# expansion_module_ARDUINO_UNO.net
KiCad netlist of a schematic drawn in EAGLE
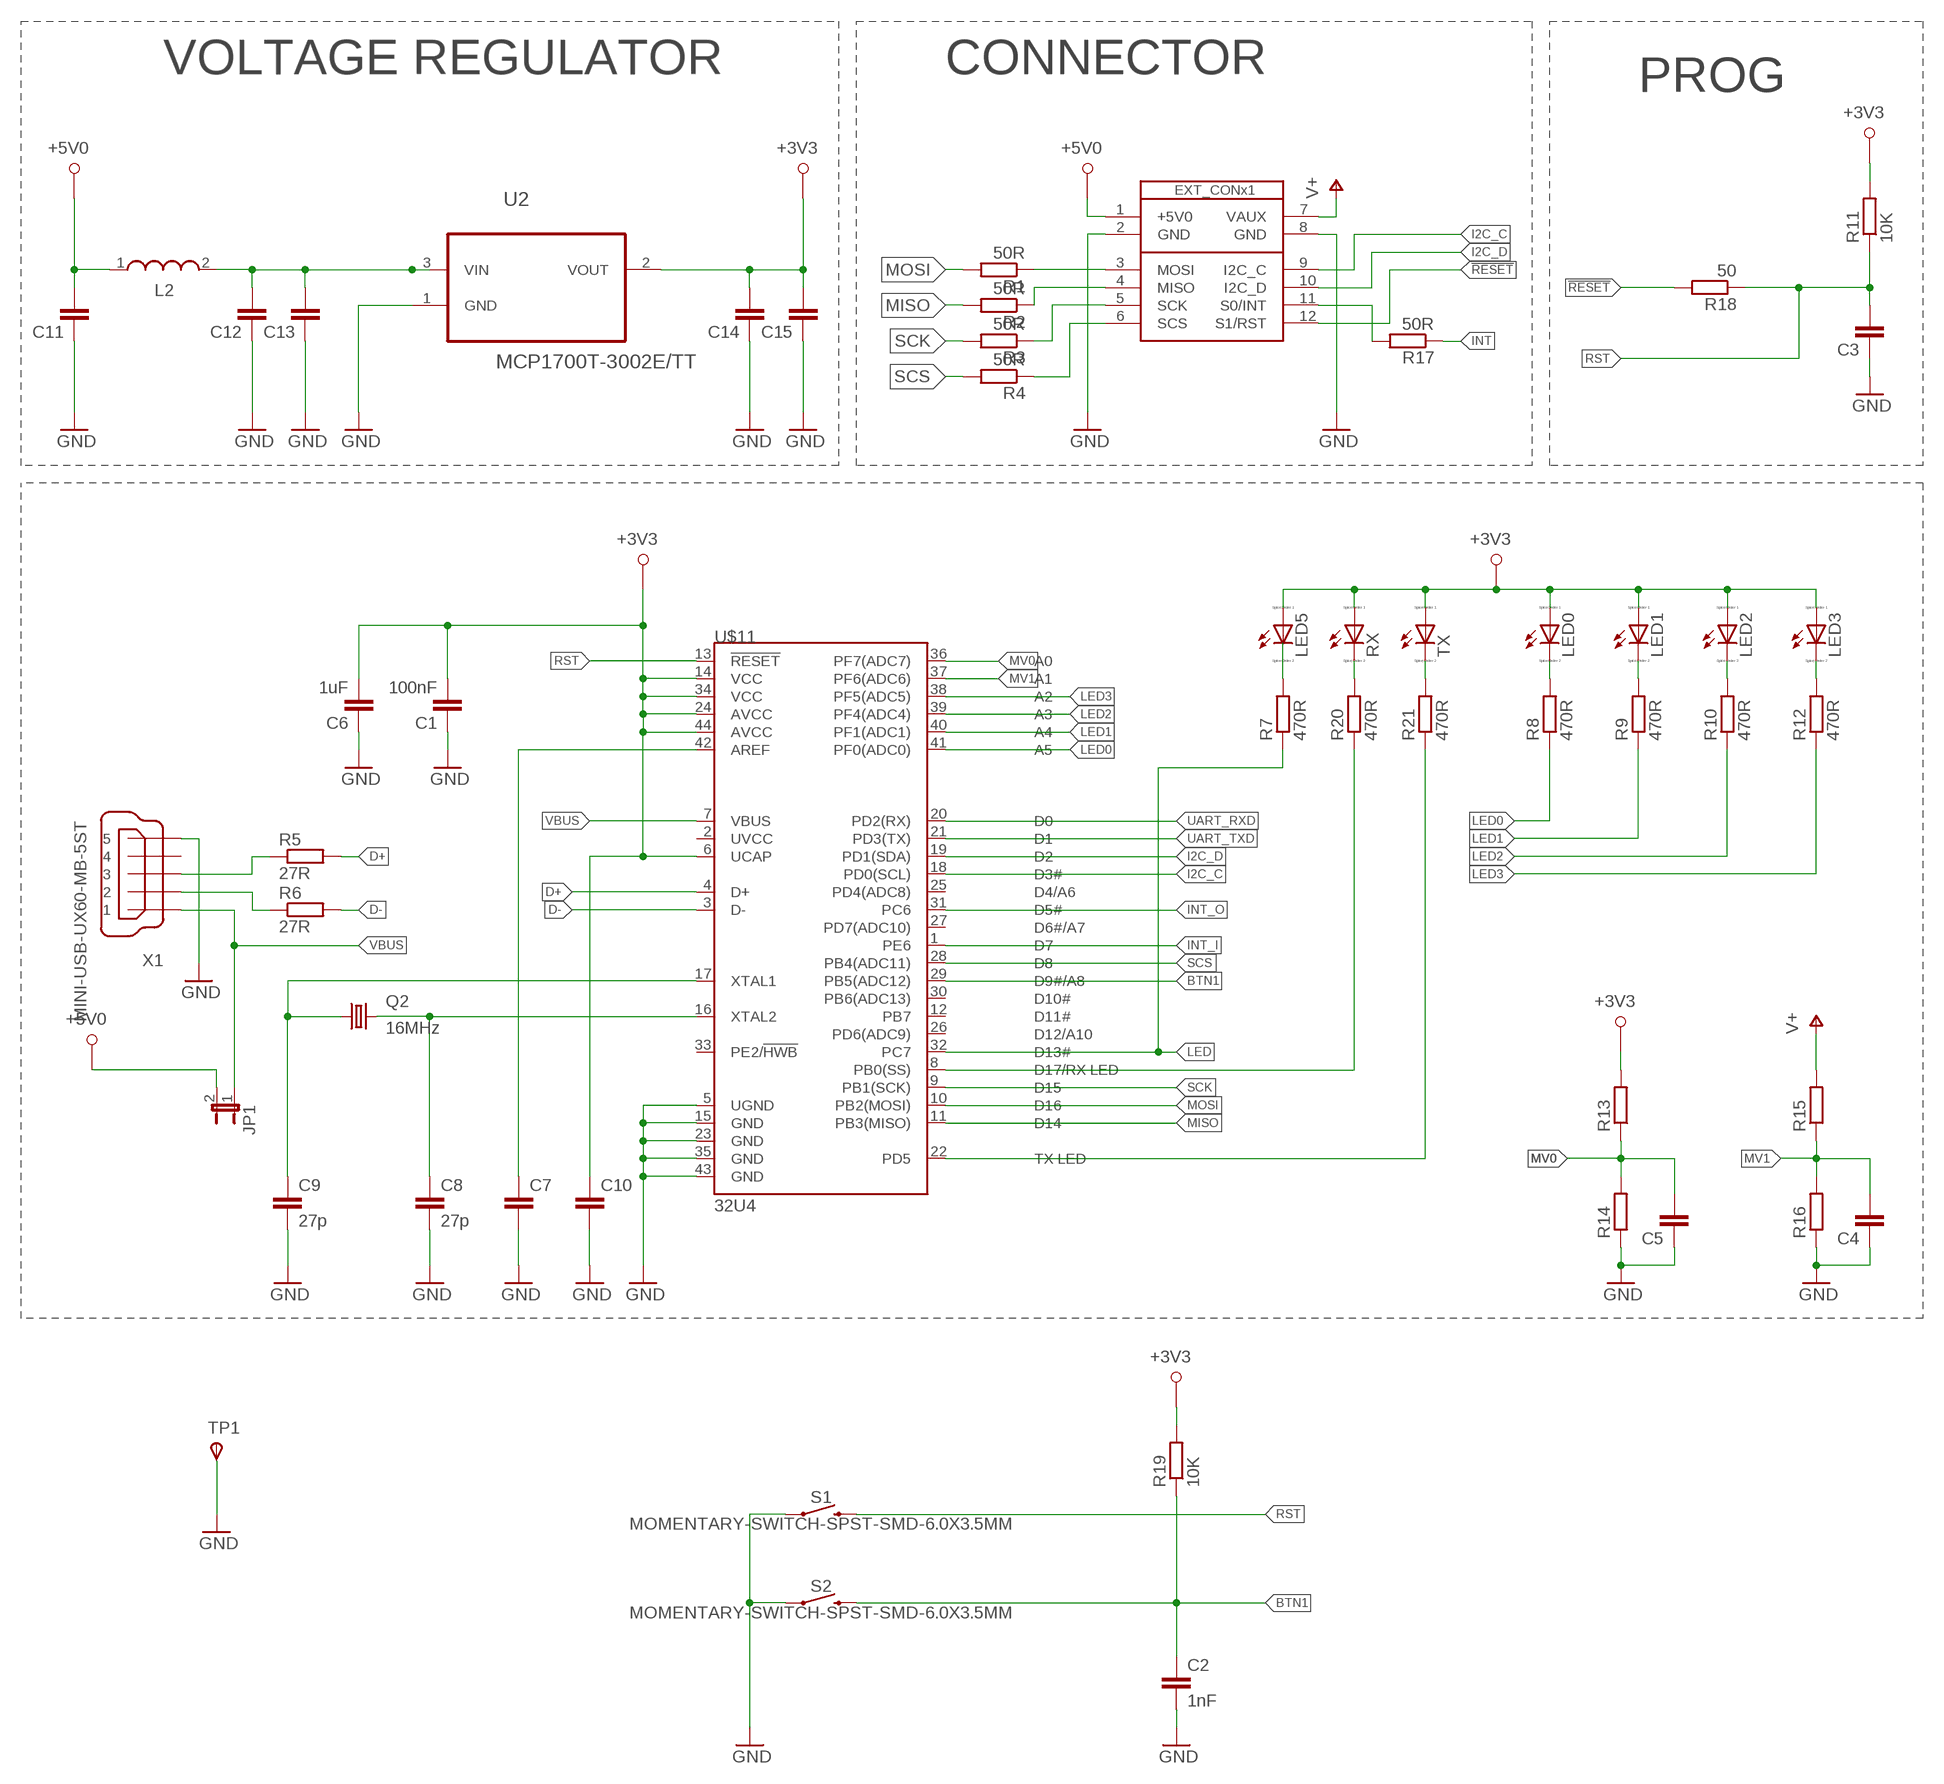
[diagram p0: schematic, sheet 1]

(export (version "E")
  (design (tool "Eeschema 10.0.6"))
  (components
    (comp (ref "C1")
      (value "100nF")
      (footprint "eagle-import:C0603")
      (libsource (lib "eagle-import") (part "resistor_C-EUC0603"))
    )
    (comp (ref "C2")
      (value "1nF")
      (footprint "eagle-import:C0603K")
      (libsource (lib "eagle-import") (part "C-EUC0603K"))
    )
    (comp (ref "C3")
      (value "C-EUC0603")
      (footprint "eagle-import:C0603")
      (libsource (lib "eagle-import") (part "resistor_C-EUC0603"))
    )
    (comp (ref "C4")
      (value "C-EUC0603")
      (footprint "eagle-import:C0603")
      (libsource (lib "eagle-import") (part "resistor_C-EUC0603"))
    )
    (comp (ref "C5")
      (value "C-EUC0603")
      (footprint "eagle-import:C0603")
      (libsource (lib "eagle-import") (part "resistor_C-EUC0603"))
    )
    (comp (ref "C6")
      (value "1uF")
      (footprint "eagle-import:C0603")
      (libsource (lib "eagle-import") (part "resistor_C-EUC0603"))
    )
    (comp (ref "C7")
      (value "C-EUC0603K")
      (footprint "eagle-import:C0603K")
      (libsource (lib "eagle-import") (part "C-EUC0603K"))
    )
    (comp (ref "C8")
      (value "27p")
      (footprint "eagle-import:C0603K")
      (libsource (lib "eagle-import") (part "C-EUC0603K"))
    )
    (comp (ref "C9")
      (value "27p")
      (footprint "eagle-import:C0603K")
      (libsource (lib "eagle-import") (part "C-EUC0603K"))
    )
    (comp (ref "C10")
      (value "C-EUC0603K")
      (footprint "eagle-import:C0603K")
      (libsource (lib "eagle-import") (part "C-EUC0603K"))
    )
    (comp (ref "C11")
      (value "C-EUC0603")
      (footprint "eagle-import:C0603")
      (libsource (lib "eagle-import") (part "resistor_C-EUC0603"))
    )
    (comp (ref "C12")
      (value "C-EUC0603")
      (footprint "eagle-import:C0603")
      (libsource (lib "eagle-import") (part "resistor_C-EUC0603"))
    )
    (comp (ref "C13")
      (value "C-EUC0603")
      (footprint "eagle-import:C0603")
      (libsource (lib "eagle-import") (part "resistor_C-EUC0603"))
    )
    (comp (ref "C14")
      (value "C-EUC0603")
      (footprint "eagle-import:C0603")
      (libsource (lib "eagle-import") (part "resistor_C-EUC0603"))
    )
    (comp (ref "C15")
      (value "C-EUC0603")
      (footprint "eagle-import:C0603")
      (libsource (lib "eagle-import") (part "resistor_C-EUC0603"))
    )
    (comp (ref "JP1")
      (value "JP1E")
      (footprint "eagle-import:JP1")
      (libsource (lib "eagle-import") (part "JP1E"))
    )
    (comp (ref "L2")
      (value "WE-LQ_1210")
      (footprint "eagle-import:WE-LQ_M")
      (libsource (lib "eagle-import") (part "WE-LQ_1210"))
    )
    (comp (ref "LED0")
      (value "LED_ESML0603")
      (footprint "eagle-import:LED_SML0603")
      (libsource (lib "eagle-import") (part "LED_ESML0603"))
    )
    (comp (ref "LED1")
      (value "LED_ESML0603")
      (footprint "eagle-import:LED_SML0603")
      (libsource (lib "eagle-import") (part "LED_ESML0603"))
    )
    (comp (ref "LED2")
      (value "LED_ESML0603")
      (footprint "eagle-import:LED_SML0603")
      (libsource (lib "eagle-import") (part "LED_ESML0603"))
    )
    (comp (ref "LED3")
      (value "LED_ESML0603")
      (footprint "eagle-import:LED_SML0603")
      (libsource (lib "eagle-import") (part "LED_ESML0603"))
    )
    (comp (ref "LED5")
      (value "LED_ESML0603")
      (footprint "eagle-import:LED_SML0603")
      (libsource (lib "eagle-import") (part "LED_ESML0603"))
    )
    (comp (ref "Q2")
      (value "16MHz")
      (footprint "eagle-import:5.0X3.2_KX-9A")
      (libsource (lib "eagle-import") (part "KX-9A"))
    )
    (comp (ref "R1")
      (value "50R")
      (footprint "eagle-import:R0603")
      (libsource (lib "eagle-import") (part "R-EU_R0603"))
    )
    (comp (ref "R2")
      (value "50R")
      (footprint "eagle-import:R0603")
      (libsource (lib "eagle-import") (part "R-EU_R0603"))
    )
    (comp (ref "R3")
      (value "50R")
      (footprint "eagle-import:R0603")
      (libsource (lib "eagle-import") (part "R-EU_R0603"))
    )
    (comp (ref "R4")
      (value "50R")
      (footprint "eagle-import:R0603")
      (libsource (lib "eagle-import") (part "R-EU_R0603"))
    )
    (comp (ref "R5")
      (value "27R")
      (footprint "eagle-import:R0603")
      (libsource (lib "eagle-import") (part "R-EU_R0603"))
    )
    (comp (ref "R6")
      (value "27R")
      (footprint "eagle-import:R0603")
      (libsource (lib "eagle-import") (part "R-EU_R0603"))
    )
    (comp (ref "R7")
      (value "470R")
      (footprint "eagle-import:R0603")
      (libsource (lib "eagle-import") (part "R-EU_R0603"))
    )
    (comp (ref "R8")
      (value "470R")
      (footprint "eagle-import:R0603")
      (libsource (lib "eagle-import") (part "R-EU_R0603"))
    )
    (comp (ref "R9")
      (value "470R")
      (footprint "eagle-import:R0603")
      (libsource (lib "eagle-import") (part "R-EU_R0603"))
    )
    (comp (ref "R10")
      (value "470R")
      (footprint "eagle-import:R0603")
      (libsource (lib "eagle-import") (part "R-EU_R0603"))
    )
    (comp (ref "R11")
      (value "10K")
      (footprint "eagle-import:R0603")
      (libsource (lib "eagle-import") (part "R-EU_R0603"))
    )
    (comp (ref "R12")
      (value "470R")
      (footprint "eagle-import:R0603")
      (libsource (lib "eagle-import") (part "R-EU_R0603"))
    )
    (comp (ref "R13")
      (value "R-EU_R0603")
      (footprint "eagle-import:R0603")
      (libsource (lib "eagle-import") (part "R-EU_R0603"))
    )
    (comp (ref "R14")
      (value "R-EU_R0603")
      (footprint "eagle-import:R0603")
      (libsource (lib "eagle-import") (part "R-EU_R0603"))
    )
    (comp (ref "R15")
      (value "R-EU_R0603")
      (footprint "eagle-import:R0603")
      (libsource (lib "eagle-import") (part "R-EU_R0603"))
    )
    (comp (ref "R16")
      (value "R-EU_R0603")
      (footprint "eagle-import:R0603")
      (libsource (lib "eagle-import") (part "R-EU_R0603"))
    )
    (comp (ref "R17")
      (value "50R")
      (footprint "eagle-import:R0603")
      (libsource (lib "eagle-import") (part "R-EU_R0603"))
    )
    (comp (ref "R18")
      (value "50")
      (footprint "eagle-import:R0603")
      (libsource (lib "eagle-import") (part "R-EU_R0603"))
    )
    (comp (ref "R19")
      (value "10K")
      (footprint "eagle-import:R0603")
      (libsource (lib "eagle-import") (part "R-EU_R0603"))
    )
    (comp (ref "R20")
      (value "470R")
      (footprint "eagle-import:R0603")
      (libsource (lib "eagle-import") (part "R-EU_R0603"))
    )
    (comp (ref "R21")
      (value "470R")
      (footprint "eagle-import:R0603")
      (libsource (lib "eagle-import") (part "R-EU_R0603"))
    )
    (comp (ref "RX")
      (value "LED_ESML0603")
      (footprint "eagle-import:LED_SML0603")
      (libsource (lib "eagle-import") (part "LED_ESML0603"))
    )
    (comp (ref "S1")
      (value "MOMENTARY-SWITCH-SPST-SMD-6.0X3.5MM")
      (footprint "eagle-import:TACTILE_SWITCH_SMD_6.0X3.5MM")
      (libsource (lib "eagle-import") (part "MOMENTARY-SWITCH-SPST-SMD-6.0X3.5MM"))
    )
    (comp (ref "S2")
      (value "MOMENTARY-SWITCH-SPST-SMD-6.0X3.5MM")
      (footprint "eagle-import:TACTILE_SWITCH_SMD_6.0X3.5MM")
      (libsource (lib "eagle-import") (part "MOMENTARY-SWITCH-SPST-SMD-6.0X3.5MM"))
    )
    (comp (ref "TP1")
      (value "TPSPAD1-13")
      (footprint "eagle-import:P1-13")
      (libsource (lib "eagle-import") (part "TPSPAD1-13"))
    )
    (comp (ref "TX")
      (value "LED_ESML0603")
      (footprint "eagle-import:LED_SML0603")
      (libsource (lib "eagle-import") (part "LED_ESML0603"))
    )
    (comp (ref "U$1")
      (value "SB_EXT_CON_X1_SPI")
      (footprint "eagle-import:SB_EXT_CON_X1_FULL")
      (libsource (lib "eagle-import") (part "SB_EXT_CON_X1_SPI"))
    )
    (comp (ref "U$11")
      (value "32U4")
      (footprint "eagle-import:TQFP44")
      (libsource (lib "eagle-import") (part "ATMEGA32U4TQFP-44"))
    )
    (comp (ref "U2")
      (value "MCP1700T-3002E/TT")
      (footprint "eagle-import:SOT95P237X112-3N")
      (libsource (lib "eagle-import") (part "MCP1700T-3002E/TT"))
    )
    (comp (ref "X1")
      (value "MINI-USB-UX60-MB-5ST")
      (footprint "eagle-import:UX60-MB-5ST")
      (libsource (lib "eagle-import") (part "MINI-USB-UX60-MB-5ST"))
    )
  )
  (nets
    (net (code "1") (name "+3V3") (class "Default")
      (node (ref "C1") (pin "2") (pinfunction "2_2") (pintype "passive"))
      (node (ref "C10") (pin "1") (pinfunction "1_1") (pintype "passive"))
      (node (ref "C14") (pin "2") (pinfunction "2_2") (pintype "passive"))
      (node (ref "C15") (pin "2") (pinfunction "2_2") (pintype "passive"))
      (node (ref "C6") (pin "2") (pinfunction "2_2") (pintype "passive"))
      (node (ref "LED0") (pin "A") (pinfunction "A_A") (pintype "passive"))
      (node (ref "LED1") (pin "A") (pinfunction "A_A") (pintype "passive"))
      (node (ref "LED2") (pin "A") (pinfunction "A_A") (pintype "passive"))
      (node (ref "LED3") (pin "A") (pinfunction "A_A") (pintype "passive"))
      (node (ref "LED5") (pin "A") (pinfunction "A_A") (pintype "passive"))
      (node (ref "R11") (pin "2") (pinfunction "2_2") (pintype "passive"))
      (node (ref "R13") (pin "2") (pinfunction "2_2") (pintype "passive"))
      (node (ref "R19") (pin "2") (pinfunction "2_2") (pintype "passive"))
      (node (ref "RX") (pin "A") (pinfunction "A_A") (pintype "passive"))
      (node (ref "TX") (pin "A") (pinfunction "A_A") (pintype "passive"))
      (node (ref "U$11") (pin "14") (pinfunction "VCC_14") (pintype "bidirectional"))
      (node (ref "U$11") (pin "24") (pinfunction "AVCC_24") (pintype "bidirectional"))
      (node (ref "U$11") (pin "34") (pinfunction "VCC_34") (pintype "bidirectional"))
      (node (ref "U$11") (pin "44") (pinfunction "AVCC_44") (pintype "bidirectional"))
      (node (ref "U$11") (pin "6") (pinfunction "UCAP_6") (pintype "bidirectional"))
      (node (ref "U2") (pin "2") (pinfunction "VOUT_2") (pintype "output"))
    )
    (net (code "2") (name "+5V0") (class "Default")
      (node (ref "C11") (pin "2") (pinfunction "2_2") (pintype "passive"))
      (node (ref "JP1") (pin "2") (pinfunction "2_2") (pintype "passive"))
      (node (ref "L2") (pin "1") (pinfunction "1_1") (pintype "passive"))
      (node (ref "U$1") (pin "1") (pinfunction "+5V0_1") (pintype "bidirectional"))
    )
    (net (code "3") (name "/~{RESET}") (class "Default")
      (node (ref "R18") (pin "2") (pinfunction "2_2") (pintype "passive"))
      (node (ref "U$1") (pin "12") (pinfunction "S1/RST_12") (pintype "bidirectional"))
    )
    (net (code "4") (name "BTN1") (class "Default")
      (node (ref "C2") (pin "1") (pinfunction "1_1") (pintype "passive"))
      (node (ref "R19") (pin "1") (pinfunction "1_1") (pintype "passive"))
      (node (ref "S2") (pin "2") (pinfunction "2_2") (pintype "passive"))
      (node (ref "U$11") (pin "29") (pinfunction "PB5(ADC12)_29") (pintype "bidirectional"))
    )
    (net (code "5") (name "D+") (class "Default")
      (node (ref "R5") (pin "2") (pinfunction "2_2") (pintype "passive"))
      (node (ref "U$11") (pin "4") (pinfunction "D+_4") (pintype "bidirectional"))
    )
    (net (code "6") (name "D-") (class "Default")
      (node (ref "R6") (pin "2") (pinfunction "2_2") (pintype "passive"))
      (node (ref "U$11") (pin "3") (pinfunction "D-_3") (pintype "bidirectional"))
    )
    (net (code "7") (name "GND") (class "Default")
      (node (ref "C1") (pin "1") (pinfunction "1_1") (pintype "passive"))
      (node (ref "C10") (pin "2") (pinfunction "2_2") (pintype "passive"))
      (node (ref "C11") (pin "1") (pinfunction "1_1") (pintype "passive"))
      (node (ref "C12") (pin "1") (pinfunction "1_1") (pintype "passive"))
      (node (ref "C13") (pin "1") (pinfunction "1_1") (pintype "passive"))
      (node (ref "C14") (pin "1") (pinfunction "1_1") (pintype "passive"))
      (node (ref "C15") (pin "1") (pinfunction "1_1") (pintype "passive"))
      (node (ref "C2") (pin "2") (pinfunction "2_2") (pintype "passive"))
      (node (ref "C3") (pin "1") (pinfunction "1_1") (pintype "passive"))
      (node (ref "C4") (pin "1") (pinfunction "1_1") (pintype "passive"))
      (node (ref "C5") (pin "1") (pinfunction "1_1") (pintype "passive"))
      (node (ref "C6") (pin "1") (pinfunction "1_1") (pintype "passive"))
      (node (ref "C7") (pin "2") (pinfunction "2_2") (pintype "passive"))
      (node (ref "C8") (pin "2") (pinfunction "2_2") (pintype "passive"))
      (node (ref "C9") (pin "2") (pinfunction "2_2") (pintype "passive"))
      (node (ref "R14") (pin "1") (pinfunction "1_1") (pintype "passive"))
      (node (ref "R16") (pin "1") (pinfunction "1_1") (pintype "passive"))
      (node (ref "S1") (pin "1") (pinfunction "1_1") (pintype "passive"))
      (node (ref "S2") (pin "1") (pinfunction "1_1") (pintype "passive"))
      (node (ref "TP1") (pin "TP") (pinfunction "PP_TP") (pintype "input"))
      (node (ref "U$1") (pin "2") (pinfunction "GND_2") (pintype "bidirectional"))
      (node (ref "U$1") (pin "8") (pinfunction "GND_8") (pintype "bidirectional"))
      (node (ref "U$11") (pin "15") (pinfunction "GND_15") (pintype "bidirectional"))
      (node (ref "U$11") (pin "23") (pinfunction "GND_23") (pintype "bidirectional"))
      (node (ref "U$11") (pin "35") (pinfunction "GND_35") (pintype "bidirectional"))
      (node (ref "U$11") (pin "43") (pinfunction "GND_43") (pintype "bidirectional"))
      (node (ref "U$11") (pin "5") (pinfunction "UGND_5") (pintype "bidirectional"))
      (node (ref "U2") (pin "1") (pinfunction "GND_1") (pintype "passive"))
      (node (ref "X1") (pin "5") (pinfunction "5_5") (pintype "input"))
    )
    (net (code "8") (name "I2C_C") (class "Default")
      (node (ref "U$1") (pin "9") (pinfunction "I2C_C_9") (pintype "bidirectional"))
      (node (ref "U$11") (pin "18") (pinfunction "PD0(SCL)_18") (pintype "bidirectional"))
    )
    (net (code "9") (name "I2C_D") (class "Default")
      (node (ref "U$1") (pin "10") (pinfunction "I2C_D_10") (pintype "bidirectional"))
      (node (ref "U$11") (pin "19") (pinfunction "PD1(SDA)_19") (pintype "bidirectional"))
    )
    (net (code "10") (name "INT") (class "Default")
      (node (ref "R17") (pin "1") (pinfunction "1_1") (pintype "passive"))
    )
    (net (code "11") (name "INT_I") (class "Default")
      (node (ref "U$11") (pin "1") (pinfunction "PE6_1") (pintype "bidirectional"))
    )
    (net (code "12") (name "INT_O") (class "Default")
      (node (ref "U$11") (pin "31") (pinfunction "PC6_31") (pintype "bidirectional"))
    )
    (net (code "13") (name "LED") (class "Default")
      (node (ref "R7") (pin "1") (pinfunction "1_1") (pintype "passive"))
      (node (ref "U$11") (pin "32") (pinfunction "PC7_32") (pintype "bidirectional"))
    )
    (net (code "14") (name "LED0") (class "Default")
      (node (ref "R8") (pin "1") (pinfunction "1_1") (pintype "passive"))
      (node (ref "U$11") (pin "41") (pinfunction "PF0(ADC0)_41") (pintype "bidirectional"))
    )
    (net (code "15") (name "LED1") (class "Default")
      (node (ref "R9") (pin "1") (pinfunction "1_1") (pintype "passive"))
      (node (ref "U$11") (pin "40") (pinfunction "PF1(ADC1)_40") (pintype "bidirectional"))
    )
    (net (code "16") (name "LED2") (class "Default")
      (node (ref "R10") (pin "1") (pinfunction "1_1") (pintype "passive"))
      (node (ref "U$11") (pin "39") (pinfunction "PF4(ADC4)_39") (pintype "bidirectional"))
    )
    (net (code "17") (name "LED3") (class "Default")
      (node (ref "R12") (pin "1") (pinfunction "1_1") (pintype "passive"))
      (node (ref "U$11") (pin "38") (pinfunction "PF5(ADC5)_38") (pintype "bidirectional"))
    )
    (net (code "18") (name "MISO") (class "Default")
      (node (ref "R2") (pin "2") (pinfunction "2_2") (pintype "passive"))
      (node (ref "U$11") (pin "11") (pinfunction "PB3(MISO)_11") (pintype "bidirectional"))
    )
    (net (code "19") (name "MOSI") (class "Default")
      (node (ref "R1") (pin "2") (pinfunction "2_2") (pintype "passive"))
      (node (ref "U$11") (pin "10") (pinfunction "PB2(MOSI)_10") (pintype "bidirectional"))
    )
    (net (code "20") (name "MV0") (class "Default")
      (node (ref "C5") (pin "2") (pinfunction "2_2") (pintype "passive"))
      (node (ref "R13") (pin "1") (pinfunction "1_1") (pintype "passive"))
      (node (ref "R14") (pin "2") (pinfunction "2_2") (pintype "passive"))
      (node (ref "U$11") (pin "36") (pinfunction "PF7(ADC7)_36") (pintype "bidirectional"))
    )
    (net (code "21") (name "MV1") (class "Default")
      (node (ref "C4") (pin "2") (pinfunction "2_2") (pintype "passive"))
      (node (ref "R15") (pin "1") (pinfunction "1_1") (pintype "passive"))
      (node (ref "R16") (pin "2") (pinfunction "2_2") (pintype "passive"))
      (node (ref "U$11") (pin "37") (pinfunction "PF6(ADC6)_37") (pintype "bidirectional"))
    )
    (net (code "22") (name "Net-(LED0-PadC)") (class "Default")
      (node (ref "LED0") (pin "C") (pinfunction "C_C") (pintype "passive"))
      (node (ref "R8") (pin "2") (pinfunction "2_2") (pintype "passive"))
    )
    (net (code "23") (name "Net-(LED1-PadC)") (class "Default")
      (node (ref "LED1") (pin "C") (pinfunction "C_C") (pintype "passive"))
      (node (ref "R9") (pin "2") (pinfunction "2_2") (pintype "passive"))
    )
    (net (code "24") (name "Net-(LED2-PadC)") (class "Default")
      (node (ref "LED2") (pin "C") (pinfunction "C_C") (pintype "passive"))
      (node (ref "R10") (pin "2") (pinfunction "2_2") (pintype "passive"))
    )
    (net (code "25") (name "Net-(LED3-PadC)") (class "Default")
      (node (ref "LED3") (pin "C") (pinfunction "C_C") (pintype "passive"))
      (node (ref "R12") (pin "2") (pinfunction "2_2") (pintype "passive"))
    )
    (net (code "26") (name "Net-(LED5-PadC)") (class "Default")
      (node (ref "LED5") (pin "C") (pinfunction "C_C") (pintype "passive"))
      (node (ref "R7") (pin "2") (pinfunction "2_2") (pintype "passive"))
    )
    (net (code "27") (name "Net-(Q2-2)") (class "Default")
      (node (ref "C8") (pin "1") (pinfunction "1_1") (pintype "passive"))
      (node (ref "Q2") (pin "3") (pinfunction "2_3") (pintype "passive"))
      (node (ref "U$11") (pin "16") (pinfunction "XTAL2_16") (pintype "bidirectional"))
    )
    (net (code "28") (name "Net-(R5-Pad1)") (class "Default")
      (node (ref "R5") (pin "1") (pinfunction "1_1") (pintype "passive"))
      (node (ref "X1") (pin "3") (pinfunction "3_3") (pintype "input"))
    )
    (net (code "29") (name "Net-(R6-Pad1)") (class "Default")
      (node (ref "R6") (pin "1") (pinfunction "1_1") (pintype "passive"))
      (node (ref "X1") (pin "2") (pinfunction "2_2") (pintype "input"))
    )
    (net (code "30") (name "Net-(R20-Pad2)") (class "Default")
      (node (ref "R20") (pin "2") (pinfunction "2_2") (pintype "passive"))
      (node (ref "RX") (pin "C") (pinfunction "C_C") (pintype "passive"))
    )
    (net (code "31") (name "Net-(R21-Pad2)") (class "Default")
      (node (ref "R21") (pin "2") (pinfunction "2_2") (pintype "passive"))
      (node (ref "TX") (pin "C") (pinfunction "C_C") (pintype "passive"))
    )
    (net (code "32") (name "Net-(U$1-MISO)") (class "Default")
      (node (ref "R2") (pin "1") (pinfunction "1_1") (pintype "passive"))
      (node (ref "U$1") (pin "4") (pinfunction "MISO_4") (pintype "bidirectional"))
    )
    (net (code "33") (name "Net-(U$1-MOSI)") (class "Default")
      (node (ref "R1") (pin "1") (pinfunction "1_1") (pintype "passive"))
      (node (ref "U$1") (pin "3") (pinfunction "MOSI_3") (pintype "bidirectional"))
    )
    (net (code "34") (name "Net-(U$1-S0{slash}INT)") (class "Default")
      (node (ref "R17") (pin "2") (pinfunction "2_2") (pintype "passive"))
      (node (ref "U$1") (pin "11") (pinfunction "S0/INT_11") (pintype "bidirectional"))
    )
    (net (code "35") (name "Net-(U$1-SCK)") (class "Default")
      (node (ref "R3") (pin "1") (pinfunction "1_1") (pintype "passive"))
      (node (ref "U$1") (pin "5") (pinfunction "SCK_5") (pintype "bidirectional"))
    )
    (net (code "36") (name "Net-(U$1-SCS)") (class "Default")
      (node (ref "R4") (pin "1") (pinfunction "1_1") (pintype "passive"))
      (node (ref "U$1") (pin "6") (pinfunction "SCS_6") (pintype "bidirectional"))
    )
    (net (code "37") (name "Net-(U$11-AREF)") (class "Default")
      (node (ref "C7") (pin "1") (pinfunction "1_1") (pintype "passive"))
      (node (ref "U$11") (pin "42") (pinfunction "AREF_42") (pintype "bidirectional"))
    )
    (net (code "38") (name "Net-(U$11-PB0(SS))") (class "Default")
      (node (ref "R20") (pin "1") (pinfunction "1_1") (pintype "passive"))
      (node (ref "U$11") (pin "8") (pinfunction "PB0(SS)_8") (pintype "bidirectional"))
    )
    (net (code "39") (name "Net-(U$11-PD5)") (class "Default")
      (node (ref "R21") (pin "1") (pinfunction "1_1") (pintype "passive"))
      (node (ref "U$11") (pin "22") (pinfunction "PD5_22") (pintype "bidirectional"))
    )
    (net (code "40") (name "Net-(U$11-XTAL1)") (class "Default")
      (node (ref "C9") (pin "1") (pinfunction "1_1") (pintype "passive"))
      (node (ref "Q2") (pin "1") (pinfunction "1_1") (pintype "passive"))
      (node (ref "U$11") (pin "17") (pinfunction "XTAL1_17") (pintype "bidirectional"))
    )
    (net (code "41") (name "Net-(U2-VIN)") (class "Default")
      (node (ref "C12") (pin "2") (pinfunction "2_2") (pintype "passive"))
      (node (ref "C13") (pin "2") (pinfunction "2_2") (pintype "passive"))
      (node (ref "L2") (pin "2") (pinfunction "2_2") (pintype "passive"))
      (node (ref "U2") (pin "3") (pinfunction "VIN_3") (pintype "input"))
    )
    (net (code "42") (name "RST") (class "Default")
      (node (ref "C3") (pin "2") (pinfunction "2_2") (pintype "passive"))
      (node (ref "R11") (pin "1") (pinfunction "1_1") (pintype "passive"))
      (node (ref "R18") (pin "1") (pinfunction "1_1") (pintype "passive"))
      (node (ref "S1") (pin "2") (pinfunction "2_2") (pintype "passive"))
      (node (ref "U$11") (pin "13") (pinfunction "~{RESET}_13") (pintype "bidirectional"))
    )
    (net (code "43") (name "SCK") (class "Default")
      (node (ref "R3") (pin "2") (pinfunction "2_2") (pintype "passive"))
      (node (ref "U$11") (pin "9") (pinfunction "PB1(SCK)_9") (pintype "bidirectional"))
    )
    (net (code "44") (name "SCS") (class "Default")
      (node (ref "R4") (pin "2") (pinfunction "2_2") (pintype "passive"))
      (node (ref "U$11") (pin "28") (pinfunction "PB4(ADC11)_28") (pintype "bidirectional"))
    )
    (net (code "45") (name "UART_RXD") (class "Default")
      (node (ref "U$11") (pin "20") (pinfunction "PD2(RX)_20") (pintype "bidirectional"))
    )
    (net (code "46") (name "UART_TXD") (class "Default")
      (node (ref "U$11") (pin "21") (pinfunction "PD3(TX)_21") (pintype "bidirectional"))
    )
    (net (code "47") (name "V+") (class "Default")
      (node (ref "R15") (pin "2") (pinfunction "2_2") (pintype "passive"))
      (node (ref "U$1") (pin "7") (pinfunction "VAUX_7") (pintype "bidirectional"))
    )
    (net (code "48") (name "VBUS") (class "Default")
      (node (ref "JP1") (pin "1") (pinfunction "1_1") (pintype "passive"))
      (node (ref "U$11") (pin "7") (pinfunction "VBUS_7") (pintype "bidirectional"))
      (node (ref "X1") (pin "1") (pinfunction "1_1") (pintype "input"))
    )
    (net (code "49") (name "unconnected-(U$11-PB6(ADC13)-Pad30)") (class "Default")
      (node (ref "U$11") (pin "30") (pinfunction "PB6(ADC13)_30") (pintype "bidirectional"))
    )
    (net (code "50") (name "unconnected-(U$11-PB7-Pad12)") (class "Default")
      (node (ref "U$11") (pin "12") (pinfunction "PB7_12") (pintype "bidirectional"))
    )
    (net (code "51") (name "unconnected-(U$11-PD4(ADC8)-Pad25)") (class "Default")
      (node (ref "U$11") (pin "25") (pinfunction "PD4(ADC8)_25") (pintype "bidirectional"))
    )
    (net (code "52") (name "unconnected-(U$11-PD6(ADC9)-Pad26)") (class "Default")
      (node (ref "U$11") (pin "26") (pinfunction "PD6(ADC9)_26") (pintype "bidirectional"))
    )
    (net (code "53") (name "unconnected-(U$11-PD7(ADC10)-Pad27)") (class "Default")
      (node (ref "U$11") (pin "27") (pinfunction "PD7(ADC10)_27") (pintype "bidirectional"))
    )
    (net (code "54") (name "unconnected-(U$11-PE2{slash}~{HWB}-Pad33)") (class "Default")
      (node (ref "U$11") (pin "33") (pinfunction "PE2/~{HWB}_33") (pintype "bidirectional"))
    )
    (net (code "55") (name "unconnected-(U$11-UVCC-Pad2)") (class "Default")
      (node (ref "U$11") (pin "2") (pinfunction "UVCC_2") (pintype "bidirectional"))
    )
    (net (code "56") (name "unconnected-(X1-Pad4)") (class "Default")
      (node (ref "X1") (pin "4") (pinfunction "4_4") (pintype "input"))
    )
  )
)
